# zif_generic.net
KiCad netlist of a schematic drawn in EAGLE
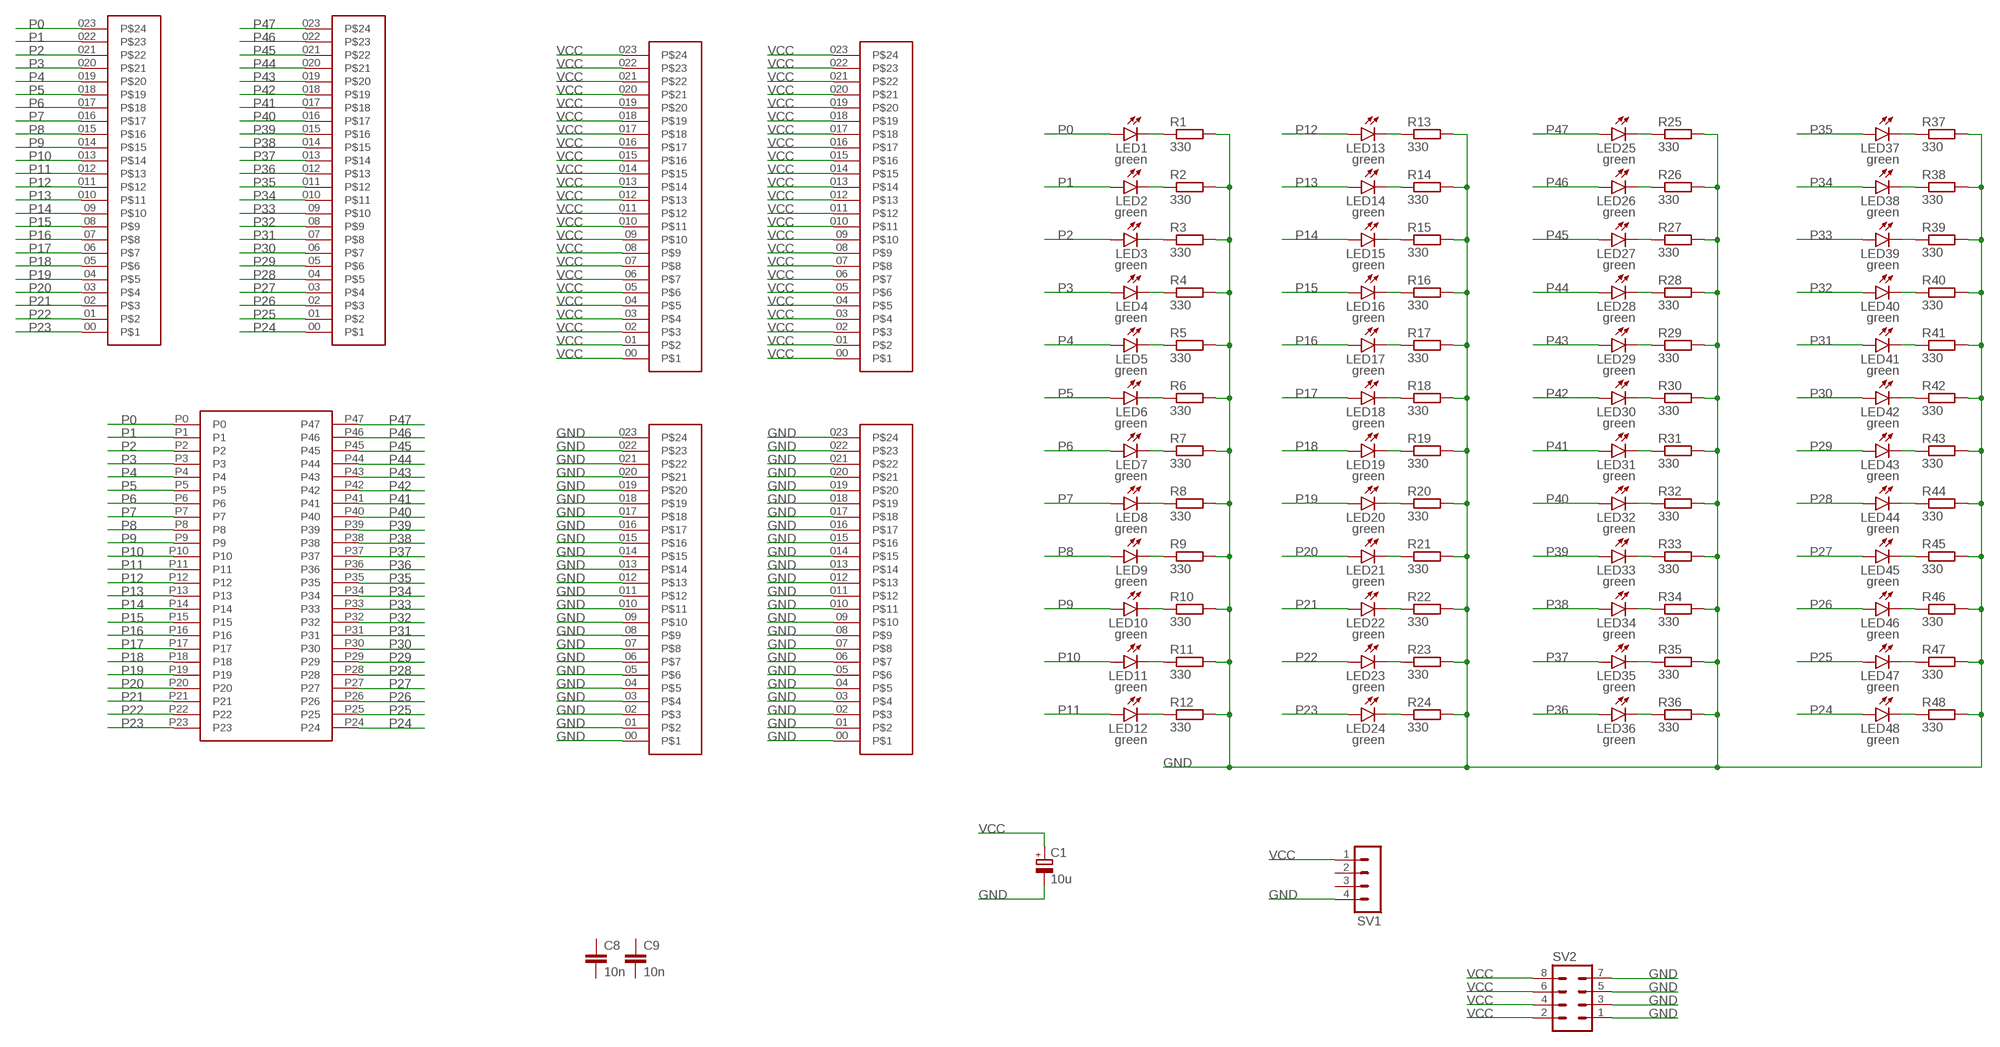
[diagram p0: schematic, sheet 1]

(export (version "E")
  (design (tool "Eeschema 10.0.6"))
  (components
    (comp (ref "C1")
      (value "10u")
      (footprint "eagle-import:E5-8,5")
      (libsource (lib "eagle-import") (part "CPOL-EUE5-8.5"))
    )
    (comp (ref "C8")
      (value "10n")
      (footprint "eagle-import:C050-025X075")
      (libsource (lib "eagle-import") (part "C-EU050-025X075"))
    )
    (comp (ref "C9")
      (value "10n")
      (footprint "eagle-import:C050-025X075")
      (libsource (lib "eagle-import") (part "C-EU050-025X075"))
    )
    (comp (ref "LED1")
      (value "green")
      (footprint "eagle-import:SML1206")
      (libsource (lib "eagle-import") (part "LEDSML1206"))
    )
    (comp (ref "LED2")
      (value "green")
      (footprint "eagle-import:SML1206")
      (libsource (lib "eagle-import") (part "LEDSML1206"))
    )
    (comp (ref "LED3")
      (value "green")
      (footprint "eagle-import:SML1206")
      (libsource (lib "eagle-import") (part "LEDSML1206"))
    )
    (comp (ref "LED4")
      (value "green")
      (footprint "eagle-import:SML1206")
      (libsource (lib "eagle-import") (part "LEDSML1206"))
    )
    (comp (ref "LED5")
      (value "green")
      (footprint "eagle-import:SML1206")
      (libsource (lib "eagle-import") (part "LEDSML1206"))
    )
    (comp (ref "LED6")
      (value "green")
      (footprint "eagle-import:SML1206")
      (libsource (lib "eagle-import") (part "LEDSML1206"))
    )
    (comp (ref "LED7")
      (value "green")
      (footprint "eagle-import:SML1206")
      (libsource (lib "eagle-import") (part "LEDSML1206"))
    )
    (comp (ref "LED8")
      (value "green")
      (footprint "eagle-import:SML1206")
      (libsource (lib "eagle-import") (part "LEDSML1206"))
    )
    (comp (ref "LED9")
      (value "green")
      (footprint "eagle-import:SML1206")
      (libsource (lib "eagle-import") (part "LEDSML1206"))
    )
    (comp (ref "LED10")
      (value "green")
      (footprint "eagle-import:SML1206")
      (libsource (lib "eagle-import") (part "LEDSML1206"))
    )
    (comp (ref "LED11")
      (value "green")
      (footprint "eagle-import:SML1206")
      (libsource (lib "eagle-import") (part "LEDSML1206"))
    )
    (comp (ref "LED12")
      (value "green")
      (footprint "eagle-import:SML1206")
      (libsource (lib "eagle-import") (part "LEDSML1206"))
    )
    (comp (ref "LED13")
      (value "green")
      (footprint "eagle-import:SML1206")
      (libsource (lib "eagle-import") (part "LEDSML1206"))
    )
    (comp (ref "LED14")
      (value "green")
      (footprint "eagle-import:SML1206")
      (libsource (lib "eagle-import") (part "LEDSML1206"))
    )
    (comp (ref "LED15")
      (value "green")
      (footprint "eagle-import:SML1206")
      (libsource (lib "eagle-import") (part "LEDSML1206"))
    )
    (comp (ref "LED16")
      (value "green")
      (footprint "eagle-import:SML1206")
      (libsource (lib "eagle-import") (part "LEDSML1206"))
    )
    (comp (ref "LED17")
      (value "green")
      (footprint "eagle-import:SML1206")
      (libsource (lib "eagle-import") (part "LEDSML1206"))
    )
    (comp (ref "LED18")
      (value "green")
      (footprint "eagle-import:SML1206")
      (libsource (lib "eagle-import") (part "LEDSML1206"))
    )
    (comp (ref "LED19")
      (value "green")
      (footprint "eagle-import:SML1206")
      (libsource (lib "eagle-import") (part "LEDSML1206"))
    )
    (comp (ref "LED20")
      (value "green")
      (footprint "eagle-import:SML1206")
      (libsource (lib "eagle-import") (part "LEDSML1206"))
    )
    (comp (ref "LED21")
      (value "green")
      (footprint "eagle-import:SML1206")
      (libsource (lib "eagle-import") (part "LEDSML1206"))
    )
    (comp (ref "LED22")
      (value "green")
      (footprint "eagle-import:SML1206")
      (libsource (lib "eagle-import") (part "LEDSML1206"))
    )
    (comp (ref "LED23")
      (value "green")
      (footprint "eagle-import:SML1206")
      (libsource (lib "eagle-import") (part "LEDSML1206"))
    )
    (comp (ref "LED24")
      (value "green")
      (footprint "eagle-import:SML1206")
      (libsource (lib "eagle-import") (part "LEDSML1206"))
    )
    (comp (ref "LED25")
      (value "green")
      (footprint "eagle-import:SML1206")
      (libsource (lib "eagle-import") (part "LEDSML1206"))
    )
    (comp (ref "LED26")
      (value "green")
      (footprint "eagle-import:SML1206")
      (libsource (lib "eagle-import") (part "LEDSML1206"))
    )
    (comp (ref "LED27")
      (value "green")
      (footprint "eagle-import:SML1206")
      (libsource (lib "eagle-import") (part "LEDSML1206"))
    )
    (comp (ref "LED28")
      (value "green")
      (footprint "eagle-import:SML1206")
      (libsource (lib "eagle-import") (part "LEDSML1206"))
    )
    (comp (ref "LED29")
      (value "green")
      (footprint "eagle-import:SML1206")
      (libsource (lib "eagle-import") (part "LEDSML1206"))
    )
    (comp (ref "LED30")
      (value "green")
      (footprint "eagle-import:SML1206")
      (libsource (lib "eagle-import") (part "LEDSML1206"))
    )
    (comp (ref "LED31")
      (value "green")
      (footprint "eagle-import:SML1206")
      (libsource (lib "eagle-import") (part "LEDSML1206"))
    )
    (comp (ref "LED32")
      (value "green")
      (footprint "eagle-import:SML1206")
      (libsource (lib "eagle-import") (part "LEDSML1206"))
    )
    (comp (ref "LED33")
      (value "green")
      (footprint "eagle-import:SML1206")
      (libsource (lib "eagle-import") (part "LEDSML1206"))
    )
    (comp (ref "LED34")
      (value "green")
      (footprint "eagle-import:SML1206")
      (libsource (lib "eagle-import") (part "LEDSML1206"))
    )
    (comp (ref "LED35")
      (value "green")
      (footprint "eagle-import:SML1206")
      (libsource (lib "eagle-import") (part "LEDSML1206"))
    )
    (comp (ref "LED36")
      (value "green")
      (footprint "eagle-import:SML1206")
      (libsource (lib "eagle-import") (part "LEDSML1206"))
    )
    (comp (ref "LED37")
      (value "green")
      (footprint "eagle-import:SML1206")
      (libsource (lib "eagle-import") (part "LEDSML1206"))
    )
    (comp (ref "LED38")
      (value "green")
      (footprint "eagle-import:SML1206")
      (libsource (lib "eagle-import") (part "LEDSML1206"))
    )
    (comp (ref "LED39")
      (value "green")
      (footprint "eagle-import:SML1206")
      (libsource (lib "eagle-import") (part "LEDSML1206"))
    )
    (comp (ref "LED40")
      (value "green")
      (footprint "eagle-import:SML1206")
      (libsource (lib "eagle-import") (part "LEDSML1206"))
    )
    (comp (ref "LED41")
      (value "green")
      (footprint "eagle-import:SML1206")
      (libsource (lib "eagle-import") (part "LEDSML1206"))
    )
    (comp (ref "LED42")
      (value "green")
      (footprint "eagle-import:SML1206")
      (libsource (lib "eagle-import") (part "LEDSML1206"))
    )
    (comp (ref "LED43")
      (value "green")
      (footprint "eagle-import:SML1206")
      (libsource (lib "eagle-import") (part "LEDSML1206"))
    )
    (comp (ref "LED44")
      (value "green")
      (footprint "eagle-import:SML1206")
      (libsource (lib "eagle-import") (part "LEDSML1206"))
    )
    (comp (ref "LED45")
      (value "green")
      (footprint "eagle-import:SML1206")
      (libsource (lib "eagle-import") (part "LEDSML1206"))
    )
    (comp (ref "LED46")
      (value "green")
      (footprint "eagle-import:SML1206")
      (libsource (lib "eagle-import") (part "LEDSML1206"))
    )
    (comp (ref "LED47")
      (value "green")
      (footprint "eagle-import:SML1206")
      (libsource (lib "eagle-import") (part "LEDSML1206"))
    )
    (comp (ref "LED48")
      (value "green")
      (footprint "eagle-import:SML1206")
      (libsource (lib "eagle-import") (part "LEDSML1206"))
    )
    (comp (ref "R1")
      (value "330")
      (footprint "eagle-import:R0805")
      (libsource (lib "eagle-import") (part "R-EU_R0805"))
    )
    (comp (ref "R2")
      (value "330")
      (footprint "eagle-import:R0805")
      (libsource (lib "eagle-import") (part "R-EU_R0805"))
    )
    (comp (ref "R3")
      (value "330")
      (footprint "eagle-import:R0805")
      (libsource (lib "eagle-import") (part "R-EU_R0805"))
    )
    (comp (ref "R4")
      (value "330")
      (footprint "eagle-import:R0805")
      (libsource (lib "eagle-import") (part "R-EU_R0805"))
    )
    (comp (ref "R5")
      (value "330")
      (footprint "eagle-import:R0805")
      (libsource (lib "eagle-import") (part "R-EU_R0805"))
    )
    (comp (ref "R6")
      (value "330")
      (footprint "eagle-import:R0805")
      (libsource (lib "eagle-import") (part "R-EU_R0805"))
    )
    (comp (ref "R7")
      (value "330")
      (footprint "eagle-import:R0805")
      (libsource (lib "eagle-import") (part "R-EU_R0805"))
    )
    (comp (ref "R8")
      (value "330")
      (footprint "eagle-import:R0805")
      (libsource (lib "eagle-import") (part "R-EU_R0805"))
    )
    (comp (ref "R9")
      (value "330")
      (footprint "eagle-import:R0805")
      (libsource (lib "eagle-import") (part "R-EU_R0805"))
    )
    (comp (ref "R10")
      (value "330")
      (footprint "eagle-import:R0805")
      (libsource (lib "eagle-import") (part "R-EU_R0805"))
    )
    (comp (ref "R11")
      (value "330")
      (footprint "eagle-import:R0805")
      (libsource (lib "eagle-import") (part "R-EU_R0805"))
    )
    (comp (ref "R12")
      (value "330")
      (footprint "eagle-import:R0805")
      (libsource (lib "eagle-import") (part "R-EU_R0805"))
    )
    (comp (ref "R13")
      (value "330")
      (footprint "eagle-import:R0805")
      (libsource (lib "eagle-import") (part "R-EU_R0805"))
    )
    (comp (ref "R14")
      (value "330")
      (footprint "eagle-import:R0805")
      (libsource (lib "eagle-import") (part "R-EU_R0805"))
    )
    (comp (ref "R15")
      (value "330")
      (footprint "eagle-import:R0805")
      (libsource (lib "eagle-import") (part "R-EU_R0805"))
    )
    (comp (ref "R16")
      (value "330")
      (footprint "eagle-import:R0805")
      (libsource (lib "eagle-import") (part "R-EU_R0805"))
    )
    (comp (ref "R17")
      (value "330")
      (footprint "eagle-import:R0805")
      (libsource (lib "eagle-import") (part "R-EU_R0805"))
    )
    (comp (ref "R18")
      (value "330")
      (footprint "eagle-import:R0805")
      (libsource (lib "eagle-import") (part "R-EU_R0805"))
    )
    (comp (ref "R19")
      (value "330")
      (footprint "eagle-import:R0805")
      (libsource (lib "eagle-import") (part "R-EU_R0805"))
    )
    (comp (ref "R20")
      (value "330")
      (footprint "eagle-import:R0805")
      (libsource (lib "eagle-import") (part "R-EU_R0805"))
    )
    (comp (ref "R21")
      (value "330")
      (footprint "eagle-import:R0805")
      (libsource (lib "eagle-import") (part "R-EU_R0805"))
    )
    (comp (ref "R22")
      (value "330")
      (footprint "eagle-import:R0805")
      (libsource (lib "eagle-import") (part "R-EU_R0805"))
    )
    (comp (ref "R23")
      (value "330")
      (footprint "eagle-import:R0805")
      (libsource (lib "eagle-import") (part "R-EU_R0805"))
    )
    (comp (ref "R24")
      (value "330")
      (footprint "eagle-import:R0805")
      (libsource (lib "eagle-import") (part "R-EU_R0805"))
    )
    (comp (ref "R25")
      (value "330")
      (footprint "eagle-import:R0805")
      (libsource (lib "eagle-import") (part "R-EU_R0805"))
    )
    (comp (ref "R26")
      (value "330")
      (footprint "eagle-import:R0805")
      (libsource (lib "eagle-import") (part "R-EU_R0805"))
    )
    (comp (ref "R27")
      (value "330")
      (footprint "eagle-import:R0805")
      (libsource (lib "eagle-import") (part "R-EU_R0805"))
    )
    (comp (ref "R28")
      (value "330")
      (footprint "eagle-import:R0805")
      (libsource (lib "eagle-import") (part "R-EU_R0805"))
    )
    (comp (ref "R29")
      (value "330")
      (footprint "eagle-import:R0805")
      (libsource (lib "eagle-import") (part "R-EU_R0805"))
    )
    (comp (ref "R30")
      (value "330")
      (footprint "eagle-import:R0805")
      (libsource (lib "eagle-import") (part "R-EU_R0805"))
    )
    (comp (ref "R31")
      (value "330")
      (footprint "eagle-import:R0805")
      (libsource (lib "eagle-import") (part "R-EU_R0805"))
    )
    (comp (ref "R32")
      (value "330")
      (footprint "eagle-import:R0805")
      (libsource (lib "eagle-import") (part "R-EU_R0805"))
    )
    (comp (ref "R33")
      (value "330")
      (footprint "eagle-import:R0805")
      (libsource (lib "eagle-import") (part "R-EU_R0805"))
    )
    (comp (ref "R34")
      (value "330")
      (footprint "eagle-import:R0805")
      (libsource (lib "eagle-import") (part "R-EU_R0805"))
    )
    (comp (ref "R35")
      (value "330")
      (footprint "eagle-import:R0805")
      (libsource (lib "eagle-import") (part "R-EU_R0805"))
    )
    (comp (ref "R36")
      (value "330")
      (footprint "eagle-import:R0805")
      (libsource (lib "eagle-import") (part "R-EU_R0805"))
    )
    (comp (ref "R37")
      (value "330")
      (footprint "eagle-import:R0805")
      (libsource (lib "eagle-import") (part "R-EU_R0805"))
    )
    (comp (ref "R38")
      (value "330")
      (footprint "eagle-import:R0805")
      (libsource (lib "eagle-import") (part "R-EU_R0805"))
    )
    (comp (ref "R39")
      (value "330")
      (footprint "eagle-import:R0805")
      (libsource (lib "eagle-import") (part "R-EU_R0805"))
    )
    (comp (ref "R40")
      (value "330")
      (footprint "eagle-import:R0805")
      (libsource (lib "eagle-import") (part "R-EU_R0805"))
    )
    (comp (ref "R41")
      (value "330")
      (footprint "eagle-import:R0805")
      (libsource (lib "eagle-import") (part "R-EU_R0805"))
    )
    (comp (ref "R42")
      (value "330")
      (footprint "eagle-import:R0805")
      (libsource (lib "eagle-import") (part "R-EU_R0805"))
    )
    (comp (ref "R43")
      (value "330")
      (footprint "eagle-import:R0805")
      (libsource (lib "eagle-import") (part "R-EU_R0805"))
    )
    (comp (ref "R44")
      (value "330")
      (footprint "eagle-import:R0805")
      (libsource (lib "eagle-import") (part "R-EU_R0805"))
    )
    (comp (ref "R45")
      (value "330")
      (footprint "eagle-import:R0805")
      (libsource (lib "eagle-import") (part "R-EU_R0805"))
    )
    (comp (ref "R46")
      (value "330")
      (footprint "eagle-import:R0805")
      (libsource (lib "eagle-import") (part "R-EU_R0805"))
    )
    (comp (ref "R47")
      (value "330")
      (footprint "eagle-import:R0805")
      (libsource (lib "eagle-import") (part "R-EU_R0805"))
    )
    (comp (ref "R48")
      (value "330")
      (footprint "eagle-import:R0805")
      (libsource (lib "eagle-import") (part "R-EU_R0805"))
    )
    (comp (ref "SV1")
      (value "MA04-1")
      (footprint "eagle-import:MA04-1")
      (libsource (lib "eagle-import") (part "MA04-1"))
    )
    (comp (ref "SV2")
      (value "MA04-2")
      (footprint "eagle-import:MA04-2")
      (libsource (lib "eagle-import") (part "MA04-2"))
    )
    (comp (ref "U$1")
      (value "PIN_1X24")
      (footprint "eagle-import:PIN_1X24")
      (libsource (lib "eagle-import") (part "PIN_1X24"))
    )
    (comp (ref "U$2")
      (value "PIN_1X24")
      (footprint "eagle-import:PIN_1X24")
      (libsource (lib "eagle-import") (part "PIN_1X24"))
    )
    (comp (ref "U$3")
      (value "PIN_1X24")
      (footprint "eagle-import:PIN_1X24")
      (libsource (lib "eagle-import") (part "PIN_1X24"))
    )
    (comp (ref "U$4")
      (value "PIN_1X24")
      (footprint "eagle-import:PIN_1X24")
      (libsource (lib "eagle-import") (part "PIN_1X24"))
    )
    (comp (ref "U$5")
      (value "PIN_1X24")
      (footprint "eagle-import:PIN_1X24")
      (libsource (lib "eagle-import") (part "PIN_1X24"))
    )
    (comp (ref "U$6")
      (value "PIN_1X24")
      (footprint "eagle-import:PIN_1X24")
      (libsource (lib "eagle-import") (part "PIN_1X24"))
    )
    (comp (ref "U$7")
      (value "ZIF_24X2")
      (footprint "eagle-import:ZIF_24X2")
      (libsource (lib "eagle-import") (part "ZIF_24X2"))
    )
  )
  (nets
    (net (code "1") (name "/GND") (class "Default")
      (node (ref "C1") (pin "-") (pinfunction "-_-") (pintype "passive"))
      (node (ref "R1") (pin "2") (pinfunction "2_2") (pintype "passive"))
      (node (ref "R10") (pin "2") (pinfunction "2_2") (pintype "passive"))
      (node (ref "R11") (pin "2") (pinfunction "2_2") (pintype "passive"))
      (node (ref "R12") (pin "2") (pinfunction "2_2") (pintype "passive"))
      (node (ref "R13") (pin "2") (pinfunction "2_2") (pintype "passive"))
      (node (ref "R14") (pin "2") (pinfunction "2_2") (pintype "passive"))
      (node (ref "R15") (pin "2") (pinfunction "2_2") (pintype "passive"))
      (node (ref "R16") (pin "2") (pinfunction "2_2") (pintype "passive"))
      (node (ref "R17") (pin "2") (pinfunction "2_2") (pintype "passive"))
      (node (ref "R18") (pin "2") (pinfunction "2_2") (pintype "passive"))
      (node (ref "R19") (pin "2") (pinfunction "2_2") (pintype "passive"))
      (node (ref "R2") (pin "2") (pinfunction "2_2") (pintype "passive"))
      (node (ref "R20") (pin "2") (pinfunction "2_2") (pintype "passive"))
      (node (ref "R21") (pin "2") (pinfunction "2_2") (pintype "passive"))
      (node (ref "R22") (pin "2") (pinfunction "2_2") (pintype "passive"))
      (node (ref "R23") (pin "2") (pinfunction "2_2") (pintype "passive"))
      (node (ref "R24") (pin "2") (pinfunction "2_2") (pintype "passive"))
      (node (ref "R25") (pin "2") (pinfunction "2_2") (pintype "passive"))
      (node (ref "R26") (pin "2") (pinfunction "2_2") (pintype "passive"))
      (node (ref "R27") (pin "2") (pinfunction "2_2") (pintype "passive"))
      (node (ref "R28") (pin "2") (pinfunction "2_2") (pintype "passive"))
      (node (ref "R29") (pin "2") (pinfunction "2_2") (pintype "passive"))
      (node (ref "R3") (pin "2") (pinfunction "2_2") (pintype "passive"))
      (node (ref "R30") (pin "2") (pinfunction "2_2") (pintype "passive"))
      (node (ref "R31") (pin "2") (pinfunction "2_2") (pintype "passive"))
      (node (ref "R32") (pin "2") (pinfunction "2_2") (pintype "passive"))
      (node (ref "R33") (pin "2") (pinfunction "2_2") (pintype "passive"))
      (node (ref "R34") (pin "2") (pinfunction "2_2") (pintype "passive"))
      (node (ref "R35") (pin "2") (pinfunction "2_2") (pintype "passive"))
      (node (ref "R36") (pin "2") (pinfunction "2_2") (pintype "passive"))
      (node (ref "R37") (pin "2") (pinfunction "2_2") (pintype "passive"))
      (node (ref "R38") (pin "2") (pinfunction "2_2") (pintype "passive"))
      (node (ref "R39") (pin "2") (pinfunction "2_2") (pintype "passive"))
      (node (ref "R4") (pin "2") (pinfunction "2_2") (pintype "passive"))
      (node (ref "R40") (pin "2") (pinfunction "2_2") (pintype "passive"))
      (node (ref "R41") (pin "2") (pinfunction "2_2") (pintype "passive"))
      (node (ref "R42") (pin "2") (pinfunction "2_2") (pintype "passive"))
      (node (ref "R43") (pin "2") (pinfunction "2_2") (pintype "passive"))
      (node (ref "R44") (pin "2") (pinfunction "2_2") (pintype "passive"))
      (node (ref "R45") (pin "2") (pinfunction "2_2") (pintype "passive"))
      (node (ref "R46") (pin "2") (pinfunction "2_2") (pintype "passive"))
      (node (ref "R47") (pin "2") (pinfunction "2_2") (pintype "passive"))
      (node (ref "R48") (pin "2") (pinfunction "2_2") (pintype "passive"))
      (node (ref "R5") (pin "2") (pinfunction "2_2") (pintype "passive"))
      (node (ref "R6") (pin "2") (pinfunction "2_2") (pintype "passive"))
      (node (ref "R7") (pin "2") (pinfunction "2_2") (pintype "passive"))
      (node (ref "R8") (pin "2") (pinfunction "2_2") (pintype "passive"))
      (node (ref "R9") (pin "2") (pinfunction "2_2") (pintype "passive"))
      (node (ref "SV1") (pin "4") (pinfunction "4_4") (pintype "passive"))
      (node (ref "SV2") (pin "1") (pinfunction "1_1") (pintype "passive"))
      (node (ref "SV2") (pin "3") (pinfunction "3_3") (pintype "passive"))
      (node (ref "SV2") (pin "5") (pinfunction "5_5") (pintype "passive"))
      (node (ref "SV2") (pin "7") (pinfunction "7_7") (pintype "passive"))
      (node (ref "U$2") (pin "00") (pinfunction "P$1_00") (pintype "bidirectional"))
      (node (ref "U$2") (pin "01") (pinfunction "P$2_01") (pintype "bidirectional"))
      (node (ref "U$2") (pin "010") (pinfunction "P$11_010") (pintype "bidirectional"))
      (node (ref "U$2") (pin "011") (pinfunction "P$12_011") (pintype "bidirectional"))
      (node (ref "U$2") (pin "012") (pinfunction "P$13_012") (pintype "bidirectional"))
      (node (ref "U$2") (pin "013") (pinfunction "P$14_013") (pintype "bidirectional"))
      (node (ref "U$2") (pin "014") (pinfunction "P$15_014") (pintype "bidirectional"))
      (node (ref "U$2") (pin "015") (pinfunction "P$16_015") (pintype "bidirectional"))
      (node (ref "U$2") (pin "016") (pinfunction "P$17_016") (pintype "bidirectional"))
      (node (ref "U$2") (pin "017") (pinfunction "P$18_017") (pintype "bidirectional"))
      (node (ref "U$2") (pin "018") (pinfunction "P$19_018") (pintype "bidirectional"))
      (node (ref "U$2") (pin "019") (pinfunction "P$20_019") (pintype "bidirectional"))
      (node (ref "U$2") (pin "02") (pinfunction "P$3_02") (pintype "bidirectional"))
      (node (ref "U$2") (pin "020") (pinfunction "P$21_020") (pintype "bidirectional"))
      (node (ref "U$2") (pin "021") (pinfunction "P$22_021") (pintype "bidirectional"))
      (node (ref "U$2") (pin "022") (pinfunction "P$23_022") (pintype "bidirectional"))
      (node (ref "U$2") (pin "023") (pinfunction "P$24_023") (pintype "bidirectional"))
      (node (ref "U$2") (pin "03") (pinfunction "P$4_03") (pintype "bidirectional"))
      (node (ref "U$2") (pin "04") (pinfunction "P$5_04") (pintype "bidirectional"))
      (node (ref "U$2") (pin "05") (pinfunction "P$6_05") (pintype "bidirectional"))
      (node (ref "U$2") (pin "06") (pinfunction "P$7_06") (pintype "bidirectional"))
      (node (ref "U$2") (pin "07") (pinfunction "P$8_07") (pintype "bidirectional"))
      (node (ref "U$2") (pin "08") (pinfunction "P$9_08") (pintype "bidirectional"))
      (node (ref "U$2") (pin "09") (pinfunction "P$10_09") (pintype "bidirectional"))
      (node (ref "U$5") (pin "00") (pinfunction "P$1_00") (pintype "bidirectional"))
      (node (ref "U$5") (pin "01") (pinfunction "P$2_01") (pintype "bidirectional"))
      (node (ref "U$5") (pin "010") (pinfunction "P$11_010") (pintype "bidirectional"))
      (node (ref "U$5") (pin "011") (pinfunction "P$12_011") (pintype "bidirectional"))
      (node (ref "U$5") (pin "012") (pinfunction "P$13_012") (pintype "bidirectional"))
      (node (ref "U$5") (pin "013") (pinfunction "P$14_013") (pintype "bidirectional"))
      (node (ref "U$5") (pin "014") (pinfunction "P$15_014") (pintype "bidirectional"))
      (node (ref "U$5") (pin "015") (pinfunction "P$16_015") (pintype "bidirectional"))
      (node (ref "U$5") (pin "016") (pinfunction "P$17_016") (pintype "bidirectional"))
      (node (ref "U$5") (pin "017") (pinfunction "P$18_017") (pintype "bidirectional"))
      (node (ref "U$5") (pin "018") (pinfunction "P$19_018") (pintype "bidirectional"))
      (node (ref "U$5") (pin "019") (pinfunction "P$20_019") (pintype "bidirectional"))
      (node (ref "U$5") (pin "02") (pinfunction "P$3_02") (pintype "bidirectional"))
      (node (ref "U$5") (pin "020") (pinfunction "P$21_020") (pintype "bidirectional"))
      (node (ref "U$5") (pin "021") (pinfunction "P$22_021") (pintype "bidirectional"))
      (node (ref "U$5") (pin "022") (pinfunction "P$23_022") (pintype "bidirectional"))
      (node (ref "U$5") (pin "023") (pinfunction "P$24_023") (pintype "bidirectional"))
      (node (ref "U$5") (pin "03") (pinfunction "P$4_03") (pintype "bidirectional"))
      (node (ref "U$5") (pin "04") (pinfunction "P$5_04") (pintype "bidirectional"))
      (node (ref "U$5") (pin "05") (pinfunction "P$6_05") (pintype "bidirectional"))
      (node (ref "U$5") (pin "06") (pinfunction "P$7_06") (pintype "bidirectional"))
      (node (ref "U$5") (pin "07") (pinfunction "P$8_07") (pintype "bidirectional"))
      (node (ref "U$5") (pin "08") (pinfunction "P$9_08") (pintype "bidirectional"))
      (node (ref "U$5") (pin "09") (pinfunction "P$10_09") (pintype "bidirectional"))
    )
    (net (code "2") (name "/P0") (class "Default")
      (node (ref "LED1") (pin "A") (pinfunction "A_A") (pintype "passive"))
      (node (ref "U$4") (pin "023") (pinfunction "P$24_023") (pintype "bidirectional"))
      (node (ref "U$7") (pin "P0") (pinfunction "P0_P0") (pintype "bidirectional"))
    )
    (net (code "3") (name "/P1") (class "Default")
      (node (ref "LED2") (pin "A") (pinfunction "A_A") (pintype "passive"))
      (node (ref "U$4") (pin "022") (pinfunction "P$23_022") (pintype "bidirectional"))
      (node (ref "U$7") (pin "P1") (pinfunction "P1_P1") (pintype "bidirectional"))
    )
    (net (code "4") (name "/P2") (class "Default")
      (node (ref "LED3") (pin "A") (pinfunction "A_A") (pintype "passive"))
      (node (ref "U$4") (pin "021") (pinfunction "P$22_021") (pintype "bidirectional"))
      (node (ref "U$7") (pin "P2") (pinfunction "P2_P2") (pintype "bidirectional"))
    )
    (net (code "5") (name "/P3") (class "Default")
      (node (ref "LED4") (pin "A") (pinfunction "A_A") (pintype "passive"))
      (node (ref "U$4") (pin "020") (pinfunction "P$21_020") (pintype "bidirectional"))
      (node (ref "U$7") (pin "P3") (pinfunction "P3_P3") (pintype "bidirectional"))
    )
    (net (code "6") (name "/P4") (class "Default")
      (node (ref "LED5") (pin "A") (pinfunction "A_A") (pintype "passive"))
      (node (ref "U$4") (pin "019") (pinfunction "P$20_019") (pintype "bidirectional"))
      (node (ref "U$7") (pin "P4") (pinfunction "P4_P4") (pintype "bidirectional"))
    )
    (net (code "7") (name "/P5") (class "Default")
      (node (ref "LED6") (pin "A") (pinfunction "A_A") (pintype "passive"))
      (node (ref "U$4") (pin "018") (pinfunction "P$19_018") (pintype "bidirectional"))
      (node (ref "U$7") (pin "P5") (pinfunction "P5_P5") (pintype "bidirectional"))
    )
    (net (code "8") (name "/P6") (class "Default")
      (node (ref "LED7") (pin "A") (pinfunction "A_A") (pintype "passive"))
      (node (ref "U$4") (pin "017") (pinfunction "P$18_017") (pintype "bidirectional"))
      (node (ref "U$7") (pin "P6") (pinfunction "P6_P6") (pintype "bidirectional"))
    )
    (net (code "9") (name "/P7") (class "Default")
      (node (ref "LED8") (pin "A") (pinfunction "A_A") (pintype "passive"))
      (node (ref "U$4") (pin "016") (pinfunction "P$17_016") (pintype "bidirectional"))
      (node (ref "U$7") (pin "P7") (pinfunction "P7_P7") (pintype "bidirectional"))
    )
    (net (code "10") (name "/P8") (class "Default")
      (node (ref "LED9") (pin "A") (pinfunction "A_A") (pintype "passive"))
      (node (ref "U$4") (pin "015") (pinfunction "P$16_015") (pintype "bidirectional"))
      (node (ref "U$7") (pin "P8") (pinfunction "P8_P8") (pintype "bidirectional"))
    )
    (net (code "11") (name "/P9") (class "Default")
      (node (ref "LED10") (pin "A") (pinfunction "A_A") (pintype "passive"))
      (node (ref "U$4") (pin "014") (pinfunction "P$15_014") (pintype "bidirectional"))
      (node (ref "U$7") (pin "P9") (pinfunction "P9_P9") (pintype "bidirectional"))
    )
    (net (code "12") (name "/P10") (class "Default")
      (node (ref "LED11") (pin "A") (pinfunction "A_A") (pintype "passive"))
      (node (ref "U$4") (pin "013") (pinfunction "P$14_013") (pintype "bidirectional"))
      (node (ref "U$7") (pin "P10") (pinfunction "P10_P10") (pintype "bidirectional"))
    )
    (net (code "13") (name "/P11") (class "Default")
      (node (ref "LED12") (pin "A") (pinfunction "A_A") (pintype "passive"))
      (node (ref "U$4") (pin "012") (pinfunction "P$13_012") (pintype "bidirectional"))
      (node (ref "U$7") (pin "P11") (pinfunction "P11_P11") (pintype "bidirectional"))
    )
    (net (code "14") (name "/P12") (class "Default")
      (node (ref "LED13") (pin "A") (pinfunction "A_A") (pintype "passive"))
      (node (ref "U$4") (pin "011") (pinfunction "P$12_011") (pintype "bidirectional"))
      (node (ref "U$7") (pin "P12") (pinfunction "P12_P12") (pintype "bidirectional"))
    )
    (net (code "15") (name "/P13") (class "Default")
      (node (ref "LED14") (pin "A") (pinfunction "A_A") (pintype "passive"))
      (node (ref "U$4") (pin "010") (pinfunction "P$11_010") (pintype "bidirectional"))
      (node (ref "U$7") (pin "P13") (pinfunction "P13_P13") (pintype "bidirectional"))
    )
    (net (code "16") (name "/P14") (class "Default")
      (node (ref "LED15") (pin "A") (pinfunction "A_A") (pintype "passive"))
      (node (ref "U$4") (pin "09") (pinfunction "P$10_09") (pintype "bidirectional"))
      (node (ref "U$7") (pin "P14") (pinfunction "P14_P14") (pintype "bidirectional"))
    )
    (net (code "17") (name "/P15") (class "Default")
      (node (ref "LED16") (pin "A") (pinfunction "A_A") (pintype "passive"))
      (node (ref "U$4") (pin "08") (pinfunction "P$9_08") (pintype "bidirectional"))
      (node (ref "U$7") (pin "P15") (pinfunction "P15_P15") (pintype "bidirectional"))
    )
    (net (code "18") (name "/P16") (class "Default")
      (node (ref "LED17") (pin "A") (pinfunction "A_A") (pintype "passive"))
      (node (ref "U$4") (pin "07") (pinfunction "P$8_07") (pintype "bidirectional"))
      (node (ref "U$7") (pin "P16") (pinfunction "P16_P16") (pintype "bidirectional"))
    )
    (net (code "19") (name "/P17") (class "Default")
      (node (ref "LED18") (pin "A") (pinfunction "A_A") (pintype "passive"))
      (node (ref "U$4") (pin "06") (pinfunction "P$7_06") (pintype "bidirectional"))
      (node (ref "U$7") (pin "P17") (pinfunction "P17_P17") (pintype "bidirectional"))
    )
    (net (code "20") (name "/P18") (class "Default")
      (node (ref "LED19") (pin "A") (pinfunction "A_A") (pintype "passive"))
      (node (ref "U$4") (pin "05") (pinfunction "P$6_05") (pintype "bidirectional"))
      (node (ref "U$7") (pin "P18") (pinfunction "P18_P18") (pintype "bidirectional"))
    )
    (net (code "21") (name "/P19") (class "Default")
      (node (ref "LED20") (pin "A") (pinfunction "A_A") (pintype "passive"))
      (node (ref "U$4") (pin "04") (pinfunction "P$5_04") (pintype "bidirectional"))
      (node (ref "U$7") (pin "P19") (pinfunction "P19_P19") (pintype "bidirectional"))
    )
    (net (code "22") (name "/P20") (class "Default")
      (node (ref "LED21") (pin "A") (pinfunction "A_A") (pintype "passive"))
      (node (ref "U$4") (pin "03") (pinfunction "P$4_03") (pintype "bidirectional"))
      (node (ref "U$7") (pin "P20") (pinfunction "P20_P20") (pintype "bidirectional"))
    )
    (net (code "23") (name "/P21") (class "Default")
      (node (ref "LED22") (pin "A") (pinfunction "A_A") (pintype "passive"))
      (node (ref "U$4") (pin "02") (pinfunction "P$3_02") (pintype "bidirectional"))
      (node (ref "U$7") (pin "P21") (pinfunction "P21_P21") (pintype "bidirectional"))
    )
    (net (code "24") (name "/P22") (class "Default")
      (node (ref "LED23") (pin "A") (pinfunction "A_A") (pintype "passive"))
      (node (ref "U$4") (pin "01") (pinfunction "P$2_01") (pintype "bidirectional"))
      (node (ref "U$7") (pin "P22") (pinfunction "P22_P22") (pintype "bidirectional"))
    )
    (net (code "25") (name "/P23") (class "Default")
      (node (ref "LED24") (pin "A") (pinfunction "A_A") (pintype "passive"))
      (node (ref "U$4") (pin "00") (pinfunction "P$1_00") (pintype "bidirectional"))
      (node (ref "U$7") (pin "P23") (pinfunction "P23_P23") (pintype "bidirectional"))
    )
    (net (code "26") (name "/P24") (class "Default")
      (node (ref "LED48") (pin "A") (pinfunction "A_A") (pintype "passive"))
      (node (ref "U$1") (pin "00") (pinfunction "P$1_00") (pintype "bidirectional"))
      (node (ref "U$7") (pin "P24") (pinfunction "P24_P24") (pintype "bidirectional"))
    )
    (net (code "27") (name "/P25") (class "Default")
      (node (ref "LED47") (pin "A") (pinfunction "A_A") (pintype "passive"))
      (node (ref "U$1") (pin "01") (pinfunction "P$2_01") (pintype "bidirectional"))
      (node (ref "U$7") (pin "P25") (pinfunction "P25_P25") (pintype "bidirectional"))
    )
    (net (code "28") (name "/P26") (class "Default")
      (node (ref "LED46") (pin "A") (pinfunction "A_A") (pintype "passive"))
      (node (ref "U$1") (pin "02") (pinfunction "P$3_02") (pintype "bidirectional"))
      (node (ref "U$7") (pin "P26") (pinfunction "P26_P26") (pintype "bidirectional"))
    )
    (net (code "29") (name "/P27") (class "Default")
      (node (ref "LED45") (pin "A") (pinfunction "A_A") (pintype "passive"))
      (node (ref "U$1") (pin "03") (pinfunction "P$4_03") (pintype "bidirectional"))
      (node (ref "U$7") (pin "P27") (pinfunction "P27_P27") (pintype "bidirectional"))
    )
    (net (code "30") (name "/P28") (class "Default")
      (node (ref "LED44") (pin "A") (pinfunction "A_A") (pintype "passive"))
      (node (ref "U$1") (pin "04") (pinfunction "P$5_04") (pintype "bidirectional"))
      (node (ref "U$7") (pin "P28") (pinfunction "P28_P28") (pintype "bidirectional"))
    )
    (net (code "31") (name "/P29") (class "Default")
      (node (ref "LED43") (pin "A") (pinfunction "A_A") (pintype "passive"))
      (node (ref "U$1") (pin "05") (pinfunction "P$6_05") (pintype "bidirectional"))
      (node (ref "U$7") (pin "P29") (pinfunction "P29_P29") (pintype "bidirectional"))
    )
    (net (code "32") (name "/P30") (class "Default")
      (node (ref "LED42") (pin "A") (pinfunction "A_A") (pintype "passive"))
      (node (ref "U$1") (pin "06") (pinfunction "P$7_06") (pintype "bidirectional"))
      (node (ref "U$7") (pin "P30") (pinfunction "P30_P30") (pintype "bidirectional"))
    )
    (net (code "33") (name "/P31") (class "Default")
      (node (ref "LED41") (pin "A") (pinfunction "A_A") (pintype "passive"))
      (node (ref "U$1") (pin "07") (pinfunction "P$8_07") (pintype "bidirectional"))
      (node (ref "U$7") (pin "P31") (pinfunction "P31_P31") (pintype "bidirectional"))
    )
    (net (code "34") (name "/P32") (class "Default")
      (node (ref "LED40") (pin "A") (pinfunction "A_A") (pintype "passive"))
      (node (ref "U$1") (pin "08") (pinfunction "P$9_08") (pintype "bidirectional"))
      (node (ref "U$7") (pin "P32") (pinfunction "P32_P32") (pintype "bidirectional"))
    )
    (net (code "35") (name "/P33") (class "Default")
      (node (ref "LED39") (pin "A") (pinfunction "A_A") (pintype "passive"))
      (node (ref "U$1") (pin "09") (pinfunction "P$10_09") (pintype "bidirectional"))
      (node (ref "U$7") (pin "P33") (pinfunction "P33_P33") (pintype "bidirectional"))
    )
    (net (code "36") (name "/P34") (class "Default")
      (node (ref "LED38") (pin "A") (pinfunction "A_A") (pintype "passive"))
      (node (ref "U$1") (pin "010") (pinfunction "P$11_010") (pintype "bidirectional"))
      (node (ref "U$7") (pin "P34") (pinfunction "P34_P34") (pintype "bidirectional"))
    )
    (net (code "37") (name "/P35") (class "Default")
      (node (ref "LED37") (pin "A") (pinfunction "A_A") (pintype "passive"))
      (node (ref "U$1") (pin "011") (pinfunction "P$12_011") (pintype "bidirectional"))
      (node (ref "U$7") (pin "P35") (pinfunction "P35_P35") (pintype "bidirectional"))
    )
    (net (code "38") (name "/P36") (class "Default")
      (node (ref "LED36") (pin "A") (pinfunction "A_A") (pintype "passive"))
      (node (ref "U$1") (pin "012") (pinfunction "P$13_012") (pintype "bidirectional"))
      (node (ref "U$7") (pin "P36") (pinfunction "P36_P36") (pintype "bidirectional"))
    )
    (net (code "39") (name "/P37") (class "Default")
      (node (ref "LED35") (pin "A") (pinfunction "A_A") (pintype "passive"))
      (node (ref "U$1") (pin "013") (pinfunction "P$14_013") (pintype "bidirectional"))
      (node (ref "U$7") (pin "P37") (pinfunction "P37_P37") (pintype "bidirectional"))
    )
    (net (code "40") (name "/P38") (class "Default")
      (node (ref "LED34") (pin "A") (pinfunction "A_A") (pintype "passive"))
      (node (ref "U$1") (pin "014") (pinfunction "P$15_014") (pintype "bidirectional"))
      (node (ref "U$7") (pin "P38") (pinfunction "P38_P38") (pintype "bidirectional"))
    )
    (net (code "41") (name "/P39") (class "Default")
      (node (ref "LED33") (pin "A") (pinfunction "A_A") (pintype "passive"))
      (node (ref "U$1") (pin "015") (pinfunction "P$16_015") (pintype "bidirectional"))
      (node (ref "U$7") (pin "P39") (pinfunction "P39_P39") (pintype "bidirectional"))
    )
    (net (code "42") (name "/P40") (class "Default")
      (node (ref "LED32") (pin "A") (pinfunction "A_A") (pintype "passive"))
      (node (ref "U$1") (pin "016") (pinfunction "P$17_016") (pintype "bidirectional"))
      (node (ref "U$7") (pin "P40") (pinfunction "P40_P40") (pintype "bidirectional"))
    )
    (net (code "43") (name "/P41") (class "Default")
      (node (ref "LED31") (pin "A") (pinfunction "A_A") (pintype "passive"))
      (node (ref "U$1") (pin "017") (pinfunction "P$18_017") (pintype "bidirectional"))
      (node (ref "U$7") (pin "P41") (pinfunction "P41_P41") (pintype "bidirectional"))
    )
    (net (code "44") (name "/P42") (class "Default")
      (node (ref "LED30") (pin "A") (pinfunction "A_A") (pintype "passive"))
      (node (ref "U$1") (pin "018") (pinfunction "P$19_018") (pintype "bidirectional"))
      (node (ref "U$7") (pin "P42") (pinfunction "P42_P42") (pintype "bidirectional"))
    )
    (net (code "45") (name "/P43") (class "Default")
      (node (ref "LED29") (pin "A") (pinfunction "A_A") (pintype "passive"))
      (node (ref "U$1") (pin "019") (pinfunction "P$20_019") (pintype "bidirectional"))
      (node (ref "U$7") (pin "P43") (pinfunction "P43_P43") (pintype "bidirectional"))
    )
    (net (code "46") (name "/P44") (class "Default")
      (node (ref "LED28") (pin "A") (pinfunction "A_A") (pintype "passive"))
      (node (ref "U$1") (pin "020") (pinfunction "P$21_020") (pintype "bidirectional"))
      (node (ref "U$7") (pin "P44") (pinfunction "P44_P44") (pintype "bidirectional"))
    )
    (net (code "47") (name "/P45") (class "Default")
      (node (ref "LED27") (pin "A") (pinfunction "A_A") (pintype "passive"))
      (node (ref "U$1") (pin "021") (pinfunction "P$22_021") (pintype "bidirectional"))
      (node (ref "U$7") (pin "P45") (pinfunction "P45_P45") (pintype "bidirectional"))
    )
    (net (code "48") (name "/P46") (class "Default")
      (node (ref "LED26") (pin "A") (pinfunction "A_A") (pintype "passive"))
      (node (ref "U$1") (pin "022") (pinfunction "P$23_022") (pintype "bidirectional"))
      (node (ref "U$7") (pin "P46") (pinfunction "P46_P46") (pintype "bidirectional"))
    )
    (net (code "49") (name "/P47") (class "Default")
      (node (ref "LED25") (pin "A") (pinfunction "A_A") (pintype "passive"))
      (node (ref "U$1") (pin "023") (pinfunction "P$24_023") (pintype "bidirectional"))
      (node (ref "U$7") (pin "P47") (pinfunction "P47_P47") (pintype "bidirectional"))
    )
    (net (code "50") (name "/VCC") (class "Default")
      (node (ref "C1") (pin "+") (pinfunction "+_+") (pintype "passive"))
      (node (ref "SV1") (pin "1") (pinfunction "1_1") (pintype "passive"))
      (node (ref "SV2") (pin "2") (pinfunction "2_2") (pintype "passive"))
      (node (ref "SV2") (pin "4") (pinfunction "4_4") (pintype "passive"))
      (node (ref "SV2") (pin "6") (pinfunction "6_6") (pintype "passive"))
      (node (ref "SV2") (pin "8") (pinfunction "8_8") (pintype "passive"))
      (node (ref "U$3") (pin "00") (pinfunction "P$1_00") (pintype "bidirectional"))
      (node (ref "U$3") (pin "01") (pinfunction "P$2_01") (pintype "bidirectional"))
      (node (ref "U$3") (pin "010") (pinfunction "P$11_010") (pintype "bidirectional"))
      (node (ref "U$3") (pin "011") (pinfunction "P$12_011") (pintype "bidirectional"))
      (node (ref "U$3") (pin "012") (pinfunction "P$13_012") (pintype "bidirectional"))
      (node (ref "U$3") (pin "013") (pinfunction "P$14_013") (pintype "bidirectional"))
      (node (ref "U$3") (pin "014") (pinfunction "P$15_014") (pintype "bidirectional"))
      (node (ref "U$3") (pin "015") (pinfunction "P$16_015") (pintype "bidirectional"))
      (node (ref "U$3") (pin "016") (pinfunction "P$17_016") (pintype "bidirectional"))
      (node (ref "U$3") (pin "017") (pinfunction "P$18_017") (pintype "bidirectional"))
      (node (ref "U$3") (pin "018") (pinfunction "P$19_018") (pintype "bidirectional"))
      (node (ref "U$3") (pin "019") (pinfunction "P$20_019") (pintype "bidirectional"))
      (node (ref "U$3") (pin "02") (pinfunction "P$3_02") (pintype "bidirectional"))
      (node (ref "U$3") (pin "020") (pinfunction "P$21_020") (pintype "bidirectional"))
      (node (ref "U$3") (pin "021") (pinfunction "P$22_021") (pintype "bidirectional"))
      (node (ref "U$3") (pin "022") (pinfunction "P$23_022") (pintype "bidirectional"))
      (node (ref "U$3") (pin "023") (pinfunction "P$24_023") (pintype "bidirectional"))
      (node (ref "U$3") (pin "03") (pinfunction "P$4_03") (pintype "bidirectional"))
      (node (ref "U$3") (pin "04") (pinfunction "P$5_04") (pintype "bidirectional"))
      (node (ref "U$3") (pin "05") (pinfunction "P$6_05") (pintype "bidirectional"))
      (node (ref "U$3") (pin "06") (pinfunction "P$7_06") (pintype "bidirectional"))
      (node (ref "U$3") (pin "07") (pinfunction "P$8_07") (pintype "bidirectional"))
      (node (ref "U$3") (pin "08") (pinfunction "P$9_08") (pintype "bidirectional"))
      (node (ref "U$3") (pin "09") (pinfunction "P$10_09") (pintype "bidirectional"))
      (node (ref "U$6") (pin "00") (pinfunction "P$1_00") (pintype "bidirectional"))
      (node (ref "U$6") (pin "01") (pinfunction "P$2_01") (pintype "bidirectional"))
      (node (ref "U$6") (pin "010") (pinfunction "P$11_010") (pintype "bidirectional"))
      (node (ref "U$6") (pin "011") (pinfunction "P$12_011") (pintype "bidirectional"))
      (node (ref "U$6") (pin "012") (pinfunction "P$13_012") (pintype "bidirectional"))
      (node (ref "U$6") (pin "013") (pinfunction "P$14_013") (pintype "bidirectional"))
      (node (ref "U$6") (pin "014") (pinfunction "P$15_014") (pintype "bidirectional"))
      (node (ref "U$6") (pin "015") (pinfunction "P$16_015") (pintype "bidirectional"))
      (node (ref "U$6") (pin "016") (pinfunction "P$17_016") (pintype "bidirectional"))
      (node (ref "U$6") (pin "017") (pinfunction "P$18_017") (pintype "bidirectional"))
      (node (ref "U$6") (pin "018") (pinfunction "P$19_018") (pintype "bidirectional"))
      (node (ref "U$6") (pin "019") (pinfunction "P$20_019") (pintype "bidirectional"))
      (node (ref "U$6") (pin "02") (pinfunction "P$3_02") (pintype "bidirectional"))
      (node (ref "U$6") (pin "020") (pinfunction "P$21_020") (pintype "bidirectional"))
      (node (ref "U$6") (pin "021") (pinfunction "P$22_021") (pintype "bidirectional"))
      (node (ref "U$6") (pin "022") (pinfunction "P$23_022") (pintype "bidirectional"))
      (node (ref "U$6") (pin "023") (pinfunction "P$24_023") (pintype "bidirectional"))
      (node (ref "U$6") (pin "03") (pinfunction "P$4_03") (pintype "bidirectional"))
      (node (ref "U$6") (pin "04") (pinfunction "P$5_04") (pintype "bidirectional"))
      (node (ref "U$6") (pin "05") (pinfunction "P$6_05") (pintype "bidirectional"))
      (node (ref "U$6") (pin "06") (pinfunction "P$7_06") (pintype "bidirectional"))
      (node (ref "U$6") (pin "07") (pinfunction "P$8_07") (pintype "bidirectional"))
      (node (ref "U$6") (pin "08") (pinfunction "P$9_08") (pintype "bidirectional"))
      (node (ref "U$6") (pin "09") (pinfunction "P$10_09") (pintype "bidirectional"))
    )
    (net (code "51") (name "Net-(LED1-PadC)") (class "Default")
      (node (ref "LED1") (pin "C") (pinfunction "C_C") (pintype "passive"))
      (node (ref "R1") (pin "1") (pinfunction "1_1") (pintype "passive"))
    )
    (net (code "52") (name "Net-(LED2-PadC)") (class "Default")
      (node (ref "LED2") (pin "C") (pinfunction "C_C") (pintype "passive"))
      (node (ref "R2") (pin "1") (pinfunction "1_1") (pintype "passive"))
    )
    (net (code "53") (name "Net-(LED3-PadC)") (class "Default")
      (node (ref "LED3") (pin "C") (pinfunction "C_C") (pintype "passive"))
      (node (ref "R3") (pin "1") (pinfunction "1_1") (pintype "passive"))
    )
    (net (code "54") (name "Net-(LED4-PadC)") (class "Default")
      (node (ref "LED4") (pin "C") (pinfunction "C_C") (pintype "passive"))
      (node (ref "R4") (pin "1") (pinfunction "1_1") (pintype "passive"))
    )
    (net (code "55") (name "Net-(LED5-PadC)") (class "Default")
      (node (ref "LED5") (pin "C") (pinfunction "C_C") (pintype "passive"))
      (node (ref "R5") (pin "1") (pinfunction "1_1") (pintype "passive"))
    )
    (net (code "56") (name "Net-(LED6-PadC)") (class "Default")
      (node (ref "LED6") (pin "C") (pinfunction "C_C") (pintype "passive"))
      (node (ref "R6") (pin "1") (pinfunction "1_1") (pintype "passive"))
    )
    (net (code "57") (name "Net-(LED7-PadC)") (class "Default")
      (node (ref "LED7") (pin "C") (pinfunction "C_C") (pintype "passive"))
      (node (ref "R7") (pin "1") (pinfunction "1_1") (pintype "passive"))
    )
    (net (code "58") (name "Net-(LED8-PadC)") (class "Default")
      (node (ref "LED8") (pin "C") (pinfunction "C_C") (pintype "passive"))
      (node (ref "R8") (pin "1") (pinfunction "1_1") (pintype "passive"))
    )
    (net (code "59") (name "Net-(LED9-PadC)") (class "Default")
      (node (ref "LED9") (pin "C") (pinfunction "C_C") (pintype "passive"))
      (node (ref "R9") (pin "1") (pinfunction "1_1") (pintype "passive"))
    )
    (net (code "60") (name "Net-(LED10-PadC)") (class "Default")
      (node (ref "LED10") (pin "C") (pinfunction "C_C") (pintype "passive"))
      (node (ref "R10") (pin "1") (pinfunction "1_1") (pintype "passive"))
    )
    (net (code "61") (name "Net-(LED11-PadC)") (class "Default")
      (node (ref "LED11") (pin "C") (pinfunction "C_C") (pintype "passive"))
      (node (ref "R11") (pin "1") (pinfunction "1_1") (pintype "passive"))
    )
    (net (code "62") (name "Net-(LED12-PadC)") (class "Default")
      (node (ref "LED12") (pin "C") (pinfunction "C_C") (pintype "passive"))
      (node (ref "R12") (pin "1") (pinfunction "1_1") (pintype "passive"))
    )
    (net (code "63") (name "Net-(LED13-PadC)") (class "Default")
      (node (ref "LED13") (pin "C") (pinfunction "C_C") (pintype "passive"))
      (node (ref "R13") (pin "1") (pinfunction "1_1") (pintype "passive"))
    )
    (net (code "64") (name "Net-(LED14-PadC)") (class "Default")
      (node (ref "LED14") (pin "C") (pinfunction "C_C") (pintype "passive"))
      (node (ref "R14") (pin "1") (pinfunction "1_1") (pintype "passive"))
    )
    (net (code "65") (name "Net-(LED15-PadC)") (class "Default")
      (node (ref "LED15") (pin "C") (pinfunction "C_C") (pintype "passive"))
      (node (ref "R15") (pin "1") (pinfunction "1_1") (pintype "passive"))
    )
    (net (code "66") (name "Net-(LED16-PadC)") (class "Default")
      (node (ref "LED16") (pin "C") (pinfunction "C_C") (pintype "passive"))
      (node (ref "R16") (pin "1") (pinfunction "1_1") (pintype "passive"))
    )
    (net (code "67") (name "Net-(LED17-PadC)") (class "Default")
      (node (ref "LED17") (pin "C") (pinfunction "C_C") (pintype "passive"))
      (node (ref "R17") (pin "1") (pinfunction "1_1") (pintype "passive"))
    )
    (net (code "68") (name "Net-(LED18-PadC)") (class "Default")
      (node (ref "LED18") (pin "C") (pinfunction "C_C") (pintype "passive"))
      (node (ref "R18") (pin "1") (pinfunction "1_1") (pintype "passive"))
    )
    (net (code "69") (name "Net-(LED19-PadC)") (class "Default")
      (node (ref "LED19") (pin "C") (pinfunction "C_C") (pintype "passive"))
      (node (ref "R19") (pin "1") (pinfunction "1_1") (pintype "passive"))
    )
    (net (code "70") (name "Net-(LED20-PadC)") (class "Default")
      (node (ref "LED20") (pin "C") (pinfunction "C_C") (pintype "passive"))
      (node (ref "R20") (pin "1") (pinfunction "1_1") (pintype "passive"))
    )
    (net (code "71") (name "Net-(LED21-PadC)") (class "Default")
      (node (ref "LED21") (pin "C") (pinfunction "C_C") (pintype "passive"))
      (node (ref "R21") (pin "1") (pinfunction "1_1") (pintype "passive"))
    )
    (net (code "72") (name "Net-(LED22-PadC)") (class "Default")
      (node (ref "LED22") (pin "C") (pinfunction "C_C") (pintype "passive"))
      (node (ref "R22") (pin "1") (pinfunction "1_1") (pintype "passive"))
    )
    (net (code "73") (name "Net-(LED23-PadC)") (class "Default")
      (node (ref "LED23") (pin "C") (pinfunction "C_C") (pintype "passive"))
      (node (ref "R23") (pin "1") (pinfunction "1_1") (pintype "passive"))
    )
    (net (code "74") (name "Net-(LED24-PadC)") (class "Default")
      (node (ref "LED24") (pin "C") (pinfunction "C_C") (pintype "passive"))
      (node (ref "R24") (pin "1") (pinfunction "1_1") (pintype "passive"))
    )
    (net (code "75") (name "Net-(LED25-PadC)") (class "Default")
      (node (ref "LED25") (pin "C") (pinfunction "C_C") (pintype "passive"))
      (node (ref "R25") (pin "1") (pinfunction "1_1") (pintype "passive"))
    )
    (net (code "76") (name "Net-(LED26-PadC)") (class "Default")
      (node (ref "LED26") (pin "C") (pinfunction "C_C") (pintype "passive"))
      (node (ref "R26") (pin "1") (pinfunction "1_1") (pintype "passive"))
    )
    (net (code "77") (name "Net-(LED27-PadC)") (class "Default")
      (node (ref "LED27") (pin "C") (pinfunction "C_C") (pintype "passive"))
      (node (ref "R27") (pin "1") (pinfunction "1_1") (pintype "passive"))
    )
    (net (code "78") (name "Net-(LED28-PadC)") (class "Default")
      (node (ref "LED28") (pin "C") (pinfunction "C_C") (pintype "passive"))
      (node (ref "R28") (pin "1") (pinfunction "1_1") (pintype "passive"))
    )
    (net (code "79") (name "Net-(LED29-PadC)") (class "Default")
      (node (ref "LED29") (pin "C") (pinfunction "C_C") (pintype "passive"))
      (node (ref "R29") (pin "1") (pinfunction "1_1") (pintype "passive"))
    )
    (net (code "80") (name "Net-(LED30-PadC)") (class "Default")
      (node (ref "LED30") (pin "C") (pinfunction "C_C") (pintype "passive"))
      (node (ref "R30") (pin "1") (pinfunction "1_1") (pintype "passive"))
    )
    (net (code "81") (name "Net-(LED31-PadC)") (class "Default")
      (node (ref "LED31") (pin "C") (pinfunction "C_C") (pintype "passive"))
      (node (ref "R31") (pin "1") (pinfunction "1_1") (pintype "passive"))
    )
    (net (code "82") (name "Net-(LED32-PadC)") (class "Default")
      (node (ref "LED32") (pin "C") (pinfunction "C_C") (pintype "passive"))
      (node (ref "R32") (pin "1") (pinfunction "1_1") (pintype "passive"))
    )
    (net (code "83") (name "Net-(LED33-PadC)") (class "Default")
      (node (ref "LED33") (pin "C") (pinfunction "C_C") (pintype "passive"))
      (node (ref "R33") (pin "1") (pinfunction "1_1") (pintype "passive"))
    )
    (net (code "84") (name "Net-(LED34-PadC)") (class "Default")
      (node (ref "LED34") (pin "C") (pinfunction "C_C") (pintype "passive"))
      (node (ref "R34") (pin "1") (pinfunction "1_1") (pintype "passive"))
    )
    (net (code "85") (name "Net-(LED35-PadC)") (class "Default")
      (node (ref "LED35") (pin "C") (pinfunction "C_C") (pintype "passive"))
      (node (ref "R35") (pin "1") (pinfunction "1_1") (pintype "passive"))
    )
    (net (code "86") (name "Net-(LED36-PadC)") (class "Default")
      (node (ref "LED36") (pin "C") (pinfunction "C_C") (pintype "passive"))
      (node (ref "R36") (pin "1") (pinfunction "1_1") (pintype "passive"))
    )
    (net (code "87") (name "Net-(LED37-PadC)") (class "Default")
      (node (ref "LED37") (pin "C") (pinfunction "C_C") (pintype "passive"))
      (node (ref "R37") (pin "1") (pinfunction "1_1") (pintype "passive"))
    )
    (net (code "88") (name "Net-(LED38-PadC)") (class "Default")
      (node (ref "LED38") (pin "C") (pinfunction "C_C") (pintype "passive"))
      (node (ref "R38") (pin "1") (pinfunction "1_1") (pintype "passive"))
    )
    (net (code "89") (name "Net-(LED39-PadC)") (class "Default")
      (node (ref "LED39") (pin "C") (pinfunction "C_C") (pintype "passive"))
      (node (ref "R39") (pin "1") (pinfunction "1_1") (pintype "passive"))
    )
    (net (code "90") (name "Net-(LED40-PadC)") (class "Default")
      (node (ref "LED40") (pin "C") (pinfunction "C_C") (pintype "passive"))
      (node (ref "R40") (pin "1") (pinfunction "1_1") (pintype "passive"))
    )
    (net (code "91") (name "Net-(LED41-PadC)") (class "Default")
      (node (ref "LED41") (pin "C") (pinfunction "C_C") (pintype "passive"))
      (node (ref "R41") (pin "1") (pinfunction "1_1") (pintype "passive"))
    )
    (net (code "92") (name "Net-(LED42-PadC)") (class "Default")
      (node (ref "LED42") (pin "C") (pinfunction "C_C") (pintype "passive"))
      (node (ref "R42") (pin "1") (pinfunction "1_1") (pintype "passive"))
    )
    (net (code "93") (name "Net-(LED43-PadC)") (class "Default")
      (node (ref "LED43") (pin "C") (pinfunction "C_C") (pintype "passive"))
      (node (ref "R43") (pin "1") (pinfunction "1_1") (pintype "passive"))
    )
    (net (code "94") (name "Net-(LED44-PadC)") (class "Default")
      (node (ref "LED44") (pin "C") (pinfunction "C_C") (pintype "passive"))
      (node (ref "R44") (pin "1") (pinfunction "1_1") (pintype "passive"))
    )
    (net (code "95") (name "Net-(LED45-PadC)") (class "Default")
      (node (ref "LED45") (pin "C") (pinfunction "C_C") (pintype "passive"))
      (node (ref "R45") (pin "1") (pinfunction "1_1") (pintype "passive"))
    )
    (net (code "96") (name "Net-(LED46-PadC)") (class "Default")
      (node (ref "LED46") (pin "C") (pinfunction "C_C") (pintype "passive"))
      (node (ref "R46") (pin "1") (pinfunction "1_1") (pintype "passive"))
    )
    (net (code "97") (name "Net-(LED47-PadC)") (class "Default")
      (node (ref "LED47") (pin "C") (pinfunction "C_C") (pintype "passive"))
      (node (ref "R47") (pin "1") (pinfunction "1_1") (pintype "passive"))
    )
    (net (code "98") (name "Net-(LED48-PadC)") (class "Default")
      (node (ref "LED48") (pin "C") (pinfunction "C_C") (pintype "passive"))
      (node (ref "R48") (pin "1") (pinfunction "1_1") (pintype "passive"))
    )
    (net (code "99") (name "unconnected-(C8-Pad1)") (class "Default")
      (node (ref "C8") (pin "1") (pinfunction "1_1") (pintype "passive"))
    )
    (net (code "100") (name "unconnected-(C8-Pad2)") (class "Default")
      (node (ref "C8") (pin "2") (pinfunction "2_2") (pintype "passive"))
    )
    (net (code "101") (name "unconnected-(C9-Pad1)") (class "Default")
      (node (ref "C9") (pin "1") (pinfunction "1_1") (pintype "passive"))
    )
    (net (code "102") (name "unconnected-(C9-Pad2)") (class "Default")
      (node (ref "C9") (pin "2") (pinfunction "2_2") (pintype "passive"))
    )
    (net (code "103") (name "unconnected-(SV1-Pad2)") (class "Default")
      (node (ref "SV1") (pin "2") (pinfunction "2_2") (pintype "passive"))
    )
    (net (code "104") (name "unconnected-(SV1-Pad3)") (class "Default")
      (node (ref "SV1") (pin "3") (pinfunction "3_3") (pintype "passive"))
    )
  )
)
